# 19_USB_schdoc.net
KiCad netlist of a schematic drawn in Altium Designer
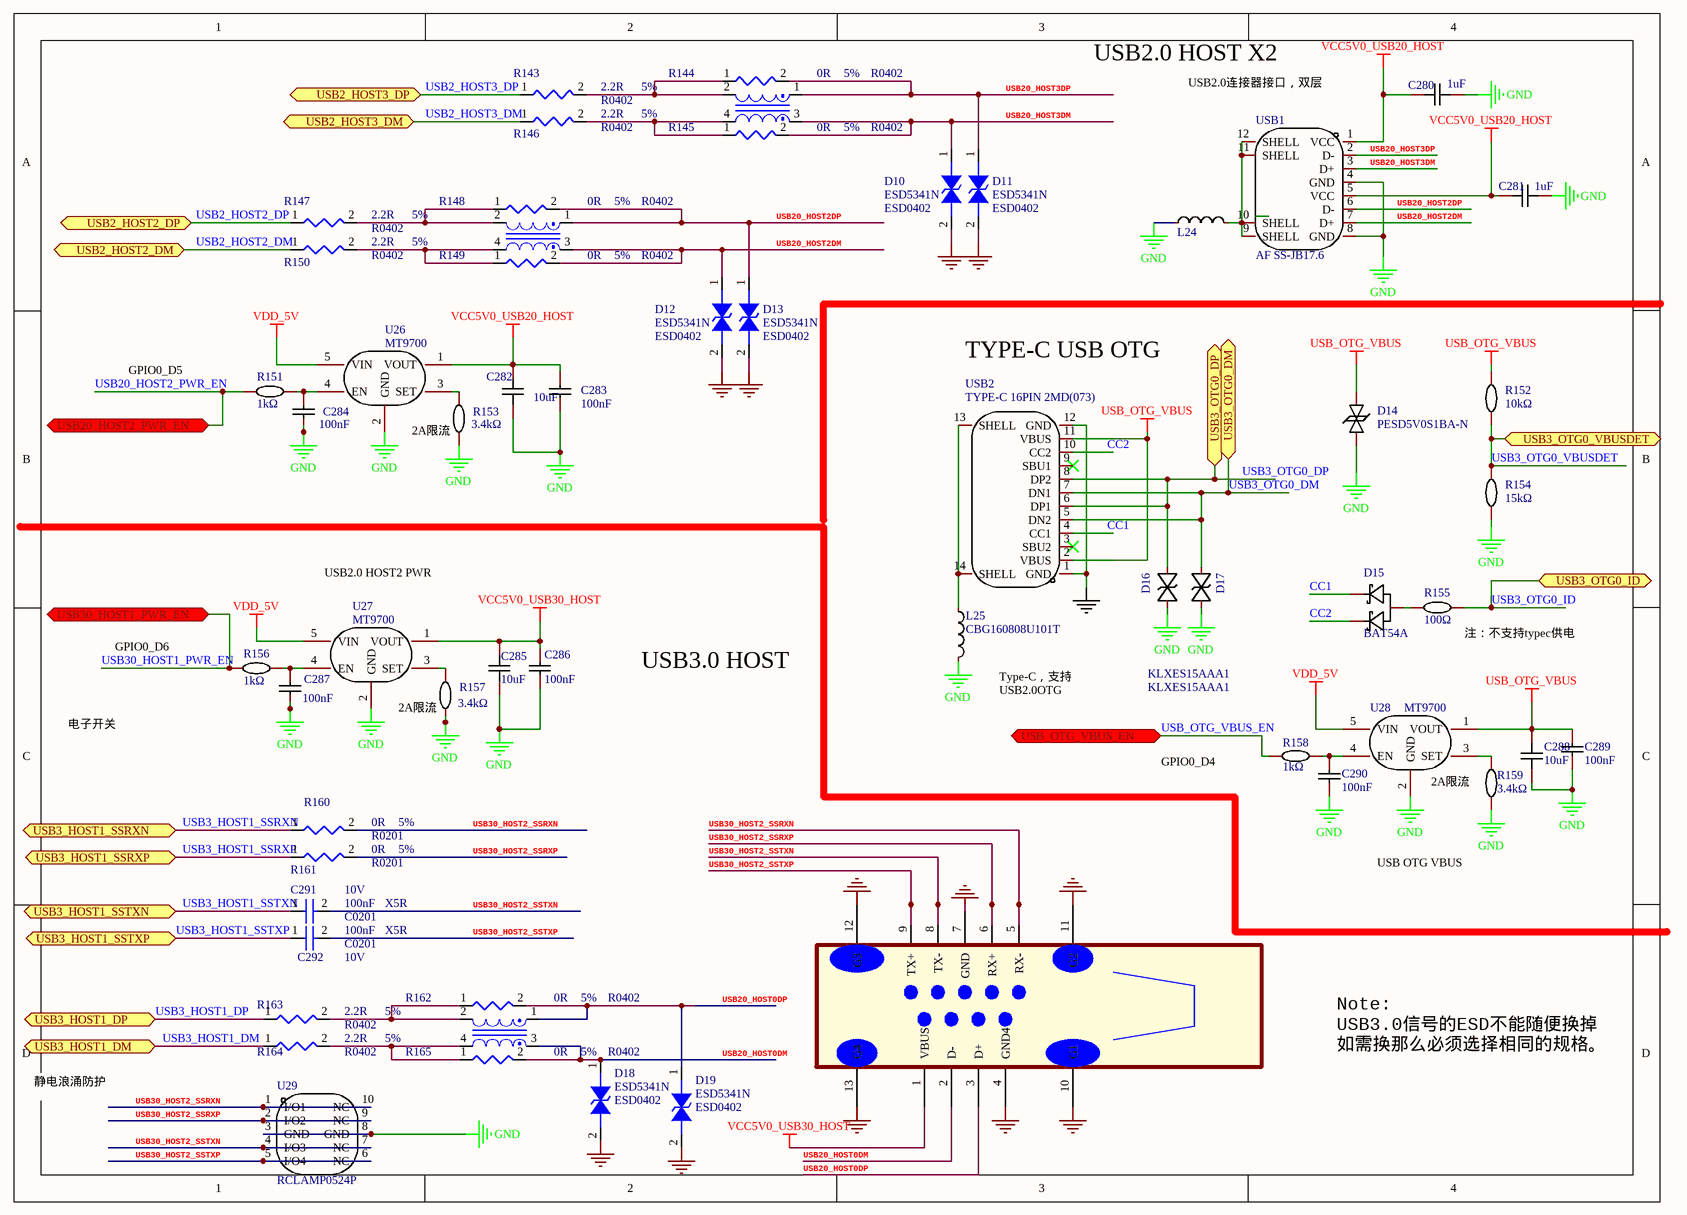
[diagram p0: 19_USB接口.schdoc.schdoc]

(export (version "E")
  (design (tool "Eeschema 10.0.6"))
  (components
    (comp (ref "C280")
      (value "1uF")
      (footprint "C0603")
      (fields
        (field (name "NAME") "1uF")
        (field (name "MANUFACTURER") "FH(风华)")
        (field (name "MANUFACTURER PART") "0603X105K100NT")
        (field (name "TOLERANCE") "±10%")
      )
      (libsource (lib "altium-import") (part "root_2_0603X105K100NT_"))
    )
    (comp (ref "C281")
      (value "1uF")
      (footprint "C0603")
      (fields
        (field (name "NAME") "1uF")
        (field (name "MANUFACTURER") "FH(风华)")
        (field (name "MANUFACTURER PART") "0603X105K100NT")
        (field (name "TOLERANCE") "±10%")
      )
      (libsource (lib "altium-import") (part "root_2_0603X105K100NT_"))
    )
    (comp (ref "C282")
      (value "10uF")
      (footprint "C0603")
      (fields
        (field (name "NAME") "10uF")
        (field (name "MANUFACTURER") "SAMSUNG(三星)")
        (field (name "MANUFACTURER PART") "CL10A106KP8NNNC")
        (field (name "TOLERANCE") "±10%")
      )
      (libsource (lib "altium-import") (part "root_3_CL10A106KP8NNNC_"))
    )
    (comp (ref "C283")
      (value "100nF")
      (footprint "C0603")
      (fields
        (field (name "NAME") "100nF")
        (field (name "MANUFACTURER") "FH(风华)")
        (field (name "MANUFACTURER PART") "0603B104K500NT")
        (field (name "TOLERANCE") "±10%")
      )
      (libsource (lib "altium-import") (part "root_3_0603B104K500NT_"))
    )
    (comp (ref "C284")
      (value "100nF")
      (footprint "C0603")
      (fields
        (field (name "NAME") "100nF")
        (field (name "MANUFACTURER") "FH(风华)")
        (field (name "MANUFACTURER PART") "0603B104K500NT")
        (field (name "TOLERANCE") "±10%")
      )
      (libsource (lib "altium-import") (part "root_1_0603B104K500NT_"))
    )
    (comp (ref "C285")
      (value "10uF")
      (footprint "C0603")
      (fields
        (field (name "NAME") "10uF")
        (field (name "MANUFACTURER") "SAMSUNG(三星)")
        (field (name "MANUFACTURER PART") "CL10A106KP8NNNC")
        (field (name "TOLERANCE") "±10%")
      )
      (libsource (lib "altium-import") (part "root_3_CL10A106KP8NNNC_"))
    )
    (comp (ref "C286")
      (value "100nF")
      (footprint "C0603")
      (fields
        (field (name "NAME") "100nF")
        (field (name "MANUFACTURER") "FH(风华)")
        (field (name "MANUFACTURER PART") "0603B104K500NT")
        (field (name "TOLERANCE") "±10%")
      )
      (libsource (lib "altium-import") (part "root_3_0603B104K500NT_"))
    )
    (comp (ref "C287")
      (value "100nF")
      (footprint "C0603")
      (fields
        (field (name "NAME") "100nF")
        (field (name "MANUFACTURER") "FH(风华)")
        (field (name "MANUFACTURER PART") "0603B104K500NT")
        (field (name "TOLERANCE") "±10%")
      )
      (libsource (lib "altium-import") (part "root_1_0603B104K500NT_"))
    )
    (comp (ref "C288")
      (value "10uF")
      (footprint "C0603")
      (fields
        (field (name "NAME") "10uF")
        (field (name "MANUFACTURER") "SAMSUNG(三星)")
        (field (name "MANUFACTURER PART") "CL10A106KP8NNNC")
        (field (name "TOLERANCE") "±10%")
      )
      (libsource (lib "altium-import") (part "root_3_CL10A106KP8NNNC_"))
    )
    (comp (ref "C289")
      (value "100nF")
      (footprint "C0603")
      (fields
        (field (name "NAME") "100nF")
        (field (name "MANUFACTURER") "FH(风华)")
        (field (name "MANUFACTURER PART") "0603B104K500NT")
        (field (name "TOLERANCE") "±10%")
      )
      (libsource (lib "altium-import") (part "root_3_0603B104K500NT_"))
    )
    (comp (ref "C290")
      (value "100nF")
      (footprint "C0603")
      (fields
        (field (name "NAME") "100nF")
        (field (name "MANUFACTURER") "FH(风华)")
        (field (name "MANUFACTURER PART") "0603B104K500NT")
        (field (name "TOLERANCE") "±10%")
      )
      (libsource (lib "altium-import") (part "root_1_0603B104K500NT_"))
    )
    (comp (ref "C291")
      (value "100nF")
      (footprint "C0201")
      (description "cap,100.00nF,+/-10%,10V,X5R,C0201")
      (fields
        (field (name "VOLTAGE") "10V")
        (field (name "PCB FOOTPRINT") "C0201")
        (field (name "DIELECTRIC") "X5R")
        (field (name "MANUFACTURER") "TDK")
        (field (name "TOLERANCE") "10%")
        (field (name "CREATED BY") "JJJ")
      )
      (libsource (lib "*") (part "CAP NP"))
    )
    (comp (ref "C292")
      (value "100nF")
      (footprint "C0201")
      (description "cap,100.00nF,+/-10%,10V,X5R,C0201")
      (fields
        (field (name "VOLTAGE") "10V")
        (field (name "PCB FOOTPRINT") "C0201")
        (field (name "DIELECTRIC") "X5R")
        (field (name "MANUFACTURER") "TDK")
        (field (name "TOLERANCE") "10%")
        (field (name "CREATED BY") "JJJ")
      )
      (libsource (lib "*") (part "CAP NP"))
    )
    (comp (ref "D10")
      (value "ESD5341N")
      (footprint "ESD0402")
      (description "1-Line, Bi-directional, Transient Voltage Suppressors.1pF.")
      (fields
        (field (name "PCB FOOTPRINT") "ESD0402")
        (field (name "MANUFACTURER") "WillSemi(韦尔半导体)")
        (field (name "CREATED BY") "JJJ")
      )
      (libsource (lib "*") (part "DIODE BI_DIR TRIG"))
    )
    (comp (ref "D11")
      (value "ESD5341N")
      (footprint "ESD0402")
      (description "1-Line, Bi-directional, Transient Voltage Suppressors.1pF.")
      (fields
        (field (name "PCB FOOTPRINT") "ESD0402")
        (field (name "MANUFACTURER") "WillSemi(韦尔半导体)")
        (field (name "CREATED BY") "JJJ")
      )
      (libsource (lib "*") (part "DIODE BI_DIR TRIG"))
    )
    (comp (ref "D12")
      (value "ESD5341N")
      (footprint "ESD0402")
      (description "1-Line, Bi-directional, Transient Voltage Suppressors.1pF.")
      (fields
        (field (name "PCB FOOTPRINT") "ESD0402")
        (field (name "MANUFACTURER") "WillSemi(韦尔半导体)")
        (field (name "CREATED BY") "JJJ")
      )
      (libsource (lib "*") (part "DIODE BI_DIR TRIG"))
    )
    (comp (ref "D13")
      (value "ESD5341N")
      (footprint "ESD0402")
      (description "1-Line, Bi-directional, Transient Voltage Suppressors.1pF.")
      (fields
        (field (name "PCB FOOTPRINT") "ESD0402")
        (field (name "MANUFACTURER") "WillSemi(韦尔半导体)")
        (field (name "CREATED BY") "JJJ")
      )
      (libsource (lib "*") (part "DIODE BI_DIR TRIG"))
    )
    (comp (ref "D14")
      (value "PESD5V0S1BA-N")
      (footprint "SOD-323_L1.8-W1.3-LS2.5-BI")
      (fields (field (name "NAME") "PESD5V0S1BA-N") (field (name "MANUFACTURER") "BORN(伯恩半导体)"))
      (libsource (lib "altium-import") (part "root_1_PESD5V0S1BA-N_"))
    )
    (comp (ref "D15")
      (value "BAT54A")
      (footprint "SOT-23-3_L2.9-W1.3-P1.90-LS2.4-BR")
      (fields (field (name "NAME") "BAT54A") (field (name "MANUFACTURER") "TWGMC(台湾迪嘉)"))
      (libsource (lib "altium-import") (part "root_3_BAT54A_C727124_"))
    )
    (comp (ref "D16")
      (value "KLXES15AAA1")
      (footprint "D0402-BI")
      (fields (field (name "NAME") "KLXES15AAA1") (field (name "MANUFACTURER") "KUU"))
      (libsource (lib "altium-import") (part "root_3_mirrored_KLXES15AAA1_"))
    )
    (comp (ref "D17")
      (value "KLXES15AAA1")
      (footprint "D0402-BI")
      (fields (field (name "NAME") "KLXES15AAA1") (field (name "MANUFACTURER") "KUU"))
      (libsource (lib "altium-import") (part "root_3_mirrored_KLXES15AAA1_"))
    )
    (comp (ref "D18")
      (value "ESD5341N")
      (footprint "ESD0402")
      (description "1-Line, Bi-directional, Transient Voltage Suppressors.1pF.")
      (fields
        (field (name "PCB FOOTPRINT") "ESD0402")
        (field (name "MANUFACTURER") "WillSemi(韦尔半导体)")
        (field (name "CREATED BY") "JJJ")
      )
      (libsource (lib "*") (part "DIODE BI_DIR TRIG"))
    )
    (comp (ref "D19")
      (value "ESD5341N")
      (footprint "ESD0402")
      (description "1-Line, Bi-directional, Transient Voltage Suppressors.1pF.")
      (fields
        (field (name "PCB FOOTPRINT") "ESD0402")
        (field (name "MANUFACTURER") "WillSemi(韦尔半导体)")
        (field (name "CREATED BY") "JJJ")
      )
      (libsource (lib "*") (part "DIODE BI_DIR TRIG"))
    )
    (comp (ref "J1")
      (value "USB30_TYPE_A_V_2")
      (footprint "USB30A9_25R70X7R32X13R85")
      (libsource (lib "RK3568核心板") (part "USB30_TYPE_A_V_2"))
    )
    (comp (ref "L22")
      (value "INDUCTOR COM")
      (footprint "RK3568核心板-13:RP2_0405")
      (libsource (lib "RK3568核心板") (part "INDUCTOR COM"))
    )
    (comp (ref "L23")
      (value "INDUCTOR COM")
      (footprint "RK3568核心板-13:RP2_0405")
      (libsource (lib "RK3568核心板") (part "INDUCTOR COM"))
    )
    (comp (ref "L24")
      (value "CBG160808U101T")
      (footprint "L0603")
      (fields (field (name "MANUFACTURER") "FH(风华)") (field (name "TOLERANCE") "±25%"))
      (libsource (lib "altium-import") (part "root_0_CBG160808U101T_"))
    )
    (comp (ref "L25")
      (value "CBG160808U101T")
      (footprint "L0603")
      (fields
        (field (name "NAME") "CBG160808U101T")
        (field (name "MANUFACTURER") "FH(风华)")
        (field (name "TOLERANCE") "±25%")
      )
      (libsource (lib "altium-import") (part "root_3_CBG160808U101T_"))
    )
    (comp (ref "L26")
      (value "INDUCTOR COM")
      (footprint "RK3568核心板-13:RP2_0405")
      (libsource (lib "RK3568核心板") (part "INDUCTOR COM"))
    )
    (comp (ref "R143")
      (value "2.2R")
      (footprint "R0402")
      (description "通用厚膜电阻,2R2,+/-5%,R0402,1/16W.")
      (fields
        (field (name "PCB FOOTPRINT") "R0402")
        (field (name "TOLERANCE") "5%")
        (field (name "MANUFACTURER") "YAGEO")
        (field (name "CREATED BY") "YTL")
      )
      (libsource (lib "*") (part "RESISTOR_Dup1"))
    )
    (comp (ref "R144")
      (value "0R")
      (footprint "R0402")
      (description "通用厚膜电阻,0R,+/-5%,R0402,1/16W.")
      (fields
        (field (name "PCB FOOTPRINT") "R0402")
        (field (name "TOLERANCE") "5%")
        (field (name "MANUFACTURER") "YAGEO")
        (field (name "CREATED BY") "YTL")
      )
      (libsource (lib "*") (part "RESISTOR_Dup1"))
    )
    (comp (ref "R145")
      (value "0R")
      (footprint "R0402")
      (description "通用厚膜电阻,0R,+/-5%,R0402,1/16W.")
      (fields
        (field (name "PCB FOOTPRINT") "R0402")
        (field (name "TOLERANCE") "5%")
        (field (name "MANUFACTURER") "YAGEO")
        (field (name "CREATED BY") "YTL")
      )
      (libsource (lib "*") (part "RESISTOR_Dup1"))
    )
    (comp (ref "R146")
      (value "2.2R")
      (footprint "R0402")
      (description "通用厚膜电阻,2R2,+/-5%,R0402,1/16W.")
      (fields
        (field (name "PCB FOOTPRINT") "R0402")
        (field (name "TOLERANCE") "5%")
        (field (name "MANUFACTURER") "YAGEO")
        (field (name "CREATED BY") "YTL")
      )
      (libsource (lib "*") (part "RESISTOR_Dup1"))
    )
    (comp (ref "R147")
      (value "2.2R")
      (footprint "R0402")
      (description "通用厚膜电阻,2R2,+/-5%,R0402,1/16W.")
      (fields
        (field (name "PCB FOOTPRINT") "R0402")
        (field (name "TOLERANCE") "5%")
        (field (name "MANUFACTURER") "YAGEO")
        (field (name "CREATED BY") "YTL")
      )
      (libsource (lib "*") (part "RESISTOR_Dup1"))
    )
    (comp (ref "R148")
      (value "0R")
      (footprint "R0402")
      (description "通用厚膜电阻,0R,+/-5%,R0402,1/16W.")
      (fields
        (field (name "PCB FOOTPRINT") "R0402")
        (field (name "TOLERANCE") "5%")
        (field (name "MANUFACTURER") "YAGEO")
        (field (name "CREATED BY") "YTL")
      )
      (libsource (lib "*") (part "RESISTOR_Dup1"))
    )
    (comp (ref "R149")
      (value "0R")
      (footprint "R0402")
      (description "通用厚膜电阻,0R,+/-5%,R0402,1/16W.")
      (fields
        (field (name "PCB FOOTPRINT") "R0402")
        (field (name "TOLERANCE") "5%")
        (field (name "MANUFACTURER") "YAGEO")
        (field (name "CREATED BY") "YTL")
      )
      (libsource (lib "*") (part "RESISTOR_Dup1"))
    )
    (comp (ref "R150")
      (value "2.2R")
      (footprint "R0402")
      (description "通用厚膜电阻,2R2,+/-5%,R0402,1/16W.")
      (fields
        (field (name "PCB FOOTPRINT") "R0402")
        (field (name "TOLERANCE") "5%")
        (field (name "MANUFACTURER") "YAGEO")
        (field (name "CREATED BY") "YTL")
      )
      (libsource (lib "*") (part "RESISTOR_Dup1"))
    )
    (comp (ref "R151")
      (value "1kΩ")
      (footprint "R0603")
      (fields
        (field (name "NAME") "1kΩ")
        (field (name "MANUFACTURER") "UNI-ROYAL(厚声)")
        (field (name "MANUFACTURER PART") "0603WAF1001T5E")
        (field (name "TOLERANCE") "±1%")
      )
      (libsource (lib "altium-import") (part "root_2_0603WAF1001T5E_"))
    )
    (comp (ref "R152")
      (value "10kΩ")
      (footprint "R0603")
      (fields
        (field (name "NAME") "10kΩ")
        (field (name "MANUFACTURER") "UNI-ROYAL(厚声)")
        (field (name "MANUFACTURER PART") "0603WAF1002T5E")
        (field (name "TOLERANCE") "±1%")
      )
      (libsource (lib "altium-import") (part "root_1_0603WAF1002T5E_"))
    )
    (comp (ref "R153")
      (value "3.4kΩ")
      (footprint "R0603")
      (fields
        (field (name "NAME") "3.4kΩ")
        (field (name "MANUFACTURER") "UNI-ROYAL(厚声)")
        (field (name "MANUFACTURER PART") "0603WAF3401T5E")
        (field (name "TOLERANCE") "±1%")
      )
      (libsource (lib "altium-import") (part "root_1_0603WAF3401T5E_"))
    )
    (comp (ref "R154")
      (value "15kΩ")
      (footprint "R0603")
      (fields
        (field (name "NAME") "15kΩ")
        (field (name "MANUFACTURER") "UNI-ROYAL(厚声)")
        (field (name "MANUFACTURER PART") "0603WAF1502T5E")
        (field (name "TOLERANCE") "±1%")
      )
      (libsource (lib "altium-import") (part "root_1_0603WAF1502T5E_"))
    )
    (comp (ref "R155")
      (value "100Ω")
      (footprint "R0603")
      (fields
        (field (name "NAME") "100Ω")
        (field (name "MANUFACTURER") "YAGEO(国巨)")
        (field (name "MANUFACTURER PART") "RC0603FR-07100RL")
        (field (name "TOLERANCE") "±1%")
      )
      (libsource (lib "altium-import") (part "root_0_RC0603FR-07100RL_"))
    )
    (comp (ref "R156")
      (value "1kΩ")
      (footprint "R0603")
      (fields
        (field (name "NAME") "1kΩ")
        (field (name "MANUFACTURER") "UNI-ROYAL(厚声)")
        (field (name "MANUFACTURER PART") "0603WAF1001T5E")
        (field (name "TOLERANCE") "±1%")
      )
      (libsource (lib "altium-import") (part "root_2_0603WAF1001T5E_"))
    )
    (comp (ref "R157")
      (value "3.4kΩ")
      (footprint "R0603")
      (fields
        (field (name "NAME") "3.4kΩ")
        (field (name "MANUFACTURER") "UNI-ROYAL(厚声)")
        (field (name "MANUFACTURER PART") "0603WAF3401T5E")
        (field (name "TOLERANCE") "±1%")
      )
      (libsource (lib "altium-import") (part "root_1_0603WAF3401T5E_"))
    )
    (comp (ref "R158")
      (value "1kΩ")
      (footprint "R0603")
      (fields
        (field (name "NAME") "1kΩ")
        (field (name "MANUFACTURER") "UNI-ROYAL(厚声)")
        (field (name "MANUFACTURER PART") "0603WAF1001T5E")
        (field (name "TOLERANCE") "±1%")
      )
      (libsource (lib "altium-import") (part "root_2_0603WAF1001T5E_"))
    )
    (comp (ref "R159")
      (value "3.4kΩ")
      (footprint "R0603")
      (fields
        (field (name "NAME") "3.4kΩ")
        (field (name "MANUFACTURER") "UNI-ROYAL(厚声)")
        (field (name "MANUFACTURER PART") "0603WAF3401T5E")
        (field (name "TOLERANCE") "±1%")
      )
      (libsource (lib "altium-import") (part "root_1_0603WAF3401T5E_"))
    )
    (comp (ref "R160")
      (value "0R")
      (footprint "R0402")
      (description "通用厚膜电阻,0R,+/-5%,R0201,1/20W.")
      (fields
        (field (name "PCB FOOTPRINT") "R0201")
        (field (name "TOLERANCE") "5%")
        (field (name "MANUFACTURER") "YAGEO")
        (field (name "CREATED BY") "YTL")
      )
      (libsource (lib "*") (part "RESISTOR_Dup1"))
    )
    (comp (ref "R161")
      (value "0R")
      (footprint "R0402")
      (description "通用厚膜电阻,0R,+/-5%,R0201,1/20W.")
      (fields
        (field (name "PCB FOOTPRINT") "R0201")
        (field (name "TOLERANCE") "5%")
        (field (name "MANUFACTURER") "YAGEO")
        (field (name "CREATED BY") "YTL")
      )
      (libsource (lib "*") (part "RESISTOR_Dup1"))
    )
    (comp (ref "R162")
      (value "0R")
      (footprint "R0402")
      (description "通用厚膜电阻,0R,+/-5%,R0402,1/16W.")
      (fields
        (field (name "PCB FOOTPRINT") "R0402")
        (field (name "TOLERANCE") "5%")
        (field (name "MANUFACTURER") "YAGEO")
        (field (name "CREATED BY") "YTL")
      )
      (libsource (lib "*") (part "RESISTOR_Dup1"))
    )
    (comp (ref "R163")
      (value "2.2R")
      (footprint "R0402")
      (description "通用厚膜电阻,2R2,+/-5%,R0402,1/16W.")
      (fields
        (field (name "PCB FOOTPRINT") "R0402")
        (field (name "TOLERANCE") "5%")
        (field (name "MANUFACTURER") "YAGEO")
        (field (name "CREATED BY") "YTL")
      )
      (libsource (lib "*") (part "RESISTOR_Dup1"))
    )
    (comp (ref "R164")
      (value "2.2R")
      (footprint "R0402")
      (description "通用厚膜电阻,2R2,+/-5%,R0402,1/16W.")
      (fields
        (field (name "PCB FOOTPRINT") "R0402")
        (field (name "TOLERANCE") "5%")
        (field (name "MANUFACTURER") "YAGEO")
        (field (name "CREATED BY") "YTL")
      )
      (libsource (lib "*") (part "RESISTOR_Dup1"))
    )
    (comp (ref "R165")
      (value "0R")
      (footprint "R0402")
      (description "通用厚膜电阻,0R,+/-5%,R0402,1/16W.")
      (fields
        (field (name "PCB FOOTPRINT") "R0402")
        (field (name "TOLERANCE") "5%")
        (field (name "MANUFACTURER") "YAGEO")
        (field (name "CREATED BY") "YTL")
      )
      (libsource (lib "*") (part "RESISTOR_Dup1"))
    )
    (comp (ref "U26")
      (value "MT9700")
      (footprint "SOT-23-5_L3.0-W1.7-P0.95-LS2.8-BR")
      (fields (field (name "NAME") "MT9700") (field (name "MANUFACTURER") "西安航天民芯"))
      (libsource (lib "altium-import") (part "root_0_mirrored_MT9700_"))
    )
    (comp (ref "U27")
      (value "MT9700")
      (footprint "SOT-23-5_L3.0-W1.7-P0.95-LS2.8-BR")
      (fields (field (name "NAME") "MT9700") (field (name "MANUFACTURER") "西安航天民芯"))
      (libsource (lib "altium-import") (part "root_0_mirrored_MT9700_"))
    )
    (comp (ref "U28")
      (value "MT9700")
      (footprint "SOT-23-5_L3.0-W1.7-P0.95-LS2.8-BR")
      (fields (field (name "NAME") "MT9700") (field (name "MANUFACTURER") "西安航天民芯"))
      (libsource (lib "altium-import") (part "root_0_mirrored_MT9700_"))
    )
    (comp (ref "U29")
      (value "RCLAMP0524P")
      (footprint "DFN2510-10_L2.5-W1.0-P0.50-BL")
      (fields (field (name "NAME") "RCLAMP0524P") (field (name "MANUFACTURER") "TECH PUBLIC(台舟)"))
      (libsource (lib "altium-import") (part "root_0_RCLAMP0524P_C907837_"))
    )
    (comp (ref "USB1")
      (value "AF SS-JB17.6")
      (footprint "USB-A-TH_AF-SS-JB17.6")
      (fields (field (name "NAME") "AF SS-JB17.6") (field (name "MANUFACTURER") "SHOU HAN(首韩)"))
      (libsource (lib "altium-import") (part "root_0_mirrored_AF SS-JB17.6_"))
    )
    (comp (ref "USB2")
      (value "TYPE-C 16PIN 2MD(073)")
      (footprint "USB-C-SMD_TYPE-C-6PIN-2MD-073")
      (fields (field (name "NAME") "TYPE-C 16PIN 2MD(073)") (field (name "MANUFACTURER") "SHOU HAN(首韩)"))
      (libsource (lib "altium-import") (part "root_2_TYPE-C 16PIN 2MD(073)_"))
    )
  )
  (nets
    (net (code "1") (name "/CC1") (class "Default")
      (node (ref "D15") (pin "1") (pinfunction "A_1") (pintype "passive"))
      (node (ref "USB2") (pin "4") (pinfunction "CC1_4") (pintype "passive"))
    )
    (net (code "2") (name "/CC2") (class "Default")
      (node (ref "D15") (pin "2") (pinfunction "A_2") (pintype "passive"))
      (node (ref "USB2") (pin "10") (pinfunction "CC2_10") (pintype "passive"))
    )
    (net (code "3") (name "/USB2_HOST2_DM") (class "Default")
      (node (ref "R150") (pin "1") (pinfunction "1_1") (pintype "passive"))
    )
    (net (code "4") (name "/USB2_HOST2_DP") (class "Default")
      (node (ref "R147") (pin "1") (pinfunction "1_1") (pintype "passive"))
    )
    (net (code "5") (name "/USB2_HOST3_DM") (class "Default")
      (node (ref "R146") (pin "1") (pinfunction "1_1") (pintype "passive"))
    )
    (net (code "6") (name "/USB2_HOST3_DP") (class "Default")
      (node (ref "R143") (pin "1") (pinfunction "1_1") (pintype "passive"))
    )
    (net (code "7") (name "/USB3_HOST1_DM") (class "Default")
      (node (ref "R164") (pin "1") (pinfunction "1_1") (pintype "passive"))
    )
    (net (code "8") (name "/USB3_HOST1_DP") (class "Default")
      (node (ref "R163") (pin "1") (pinfunction "1_1") (pintype "passive"))
    )
    (net (code "9") (name "/USB3_HOST1_SSRXN") (class "Default")
      (node (ref "R160") (pin "1") (pinfunction "1_1") (pintype "passive"))
    )
    (net (code "10") (name "/USB3_HOST1_SSRXP") (class "Default")
      (node (ref "R161") (pin "1") (pinfunction "1_1") (pintype "passive"))
    )
    (net (code "11") (name "/USB3_HOST1_SSTXN") (class "Default")
      (node (ref "C291") (pin "1") (pinfunction "1_1") (pintype "passive"))
    )
    (net (code "12") (name "/USB3_HOST1_SSTXP") (class "Default")
      (node (ref "C292") (pin "1") (pinfunction "1_1") (pintype "passive"))
    )
    (net (code "13") (name "/USB3_OTG0_DM") (class "Default")
      (node (ref "D17") (pin "1") (pinfunction "K_1") (pintype "passive"))
      (node (ref "USB2") (pin "5") (pinfunction "DN2_5") (pintype "passive"))
      (node (ref "USB2") (pin "7") (pinfunction "DN1_7") (pintype "passive"))
    )
    (net (code "14") (name "/USB3_OTG0_DP") (class "Default")
      (node (ref "D16") (pin "1") (pinfunction "K_1") (pintype "passive"))
      (node (ref "USB2") (pin "6") (pinfunction "DP1_6") (pintype "passive"))
      (node (ref "USB2") (pin "8") (pinfunction "DP2_8") (pintype "passive"))
    )
    (net (code "15") (name "/USB3_OTG0_ID") (class "Default")
      (node (ref "R155") (pin "2") (pinfunction "2_2") (pintype "passive"))
    )
    (net (code "16") (name "/USB3_OTG0_VBUSDET") (class "Default")
      (node (ref "R152") (pin "1") (pinfunction "1_1") (pintype "passive"))
      (node (ref "R154") (pin "2") (pinfunction "2_2") (pintype "passive"))
    )
    (net (code "17") (name "/USB20_HOST0DM") (class "Default")
      (node (ref "D18") (pin "1") (pinfunction "1_1") (pintype "passive"))
      (node (ref "J1") (pin "2") (pinfunction "D-_2") (pintype "passive"))
      (node (ref "L26") (pin "3") (pinfunction "3_3") (pintype "passive"))
      (node (ref "R165") (pin "2") (pinfunction "2_2") (pintype "passive"))
    )
    (net (code "18") (name "/USB20_HOST0DP") (class "Default")
      (node (ref "D19") (pin "1") (pinfunction "1_1") (pintype "passive"))
      (node (ref "J1") (pin "3") (pinfunction "D+_3") (pintype "passive"))
      (node (ref "L26") (pin "1") (pinfunction "1_1") (pintype "passive"))
      (node (ref "R162") (pin "2") (pinfunction "2_2") (pintype "passive"))
    )
    (net (code "19") (name "/USB20_HOST2DM") (class "Default")
      (node (ref "D12") (pin "1") (pinfunction "1_1") (pintype "passive"))
      (node (ref "L23") (pin "3") (pinfunction "3_3") (pintype "passive"))
      (node (ref "R149") (pin "2") (pinfunction "2_2") (pintype "passive"))
      (node (ref "USB1") (pin "7") (pinfunction "D+_7") (pintype "passive"))
    )
    (net (code "20") (name "/USB20_HOST2DP") (class "Default")
      (node (ref "D13") (pin "1") (pinfunction "1_1") (pintype "passive"))
      (node (ref "L23") (pin "1") (pinfunction "1_1") (pintype "passive"))
      (node (ref "R148") (pin "2") (pinfunction "2_2") (pintype "passive"))
      (node (ref "USB1") (pin "6") (pinfunction "D-_6") (pintype "passive"))
    )
    (net (code "21") (name "/USB20_HOST2_PWR_EN") (class "Default")
      (node (ref "R151") (pin "2") (pinfunction "2_2") (pintype "passive"))
    )
    (net (code "22") (name "/USB20_HOST3DM") (class "Default")
      (node (ref "D10") (pin "1") (pinfunction "1_1") (pintype "passive"))
      (node (ref "L22") (pin "3") (pinfunction "3_3") (pintype "passive"))
      (node (ref "R145") (pin "2") (pinfunction "2_2") (pintype "passive"))
      (node (ref "USB1") (pin "3") (pinfunction "D+_3") (pintype "passive"))
    )
    (net (code "23") (name "/USB20_HOST3DP") (class "Default")
      (node (ref "D11") (pin "1") (pinfunction "1_1") (pintype "passive"))
      (node (ref "L22") (pin "1") (pinfunction "1_1") (pintype "passive"))
      (node (ref "R144") (pin "2") (pinfunction "2_2") (pintype "passive"))
      (node (ref "USB1") (pin "2") (pinfunction "D-_2") (pintype "passive"))
    )
    (net (code "24") (name "/USB30_HOST1_PWR_EN") (class "Default")
      (node (ref "R156") (pin "2") (pinfunction "2_2") (pintype "passive"))
    )
    (net (code "25") (name "/USB30_HOST2_SSRXN") (class "Default")
      (node (ref "J1") (pin "5") (pinfunction "RX-_5") (pintype "passive"))
      (node (ref "R160") (pin "2") (pinfunction "2_2") (pintype "passive"))
      (node (ref "U29") (pin "1") (pinfunction "I/O1_1") (pintype "passive"))
      (node (ref "U29") (pin "10") (pinfunction "NC_10") (pintype "passive"))
    )
    (net (code "26") (name "/USB30_HOST2_SSRXP") (class "Default")
      (node (ref "J1") (pin "6") (pinfunction "RX+_6") (pintype "passive"))
      (node (ref "R161") (pin "2") (pinfunction "2_2") (pintype "passive"))
      (node (ref "U29") (pin "2") (pinfunction "I/O2_2") (pintype "passive"))
      (node (ref "U29") (pin "9") (pinfunction "NC_9") (pintype "passive"))
    )
    (net (code "27") (name "/USB30_HOST2_SSTXN") (class "Default")
      (node (ref "C291") (pin "2") (pinfunction "2_2") (pintype "passive"))
      (node (ref "J1") (pin "8") (pinfunction "TX-_8") (pintype "passive"))
      (node (ref "U29") (pin "4") (pinfunction "I/O3_4") (pintype "passive"))
      (node (ref "U29") (pin "7") (pinfunction "NC_7") (pintype "passive"))
    )
    (net (code "28") (name "/USB30_HOST2_SSTXP") (class "Default")
      (node (ref "C292") (pin "2") (pinfunction "2_2") (pintype "passive"))
      (node (ref "J1") (pin "9") (pinfunction "TX+_9") (pintype "passive"))
      (node (ref "U29") (pin "5") (pinfunction "I/O4_5") (pintype "passive"))
      (node (ref "U29") (pin "6") (pinfunction "NC_6") (pintype "passive"))
    )
    (net (code "29") (name "/USB_OTG_VBUS_EN") (class "Default")
      (node (ref "R158") (pin "2") (pinfunction "2_2") (pintype "passive"))
    )
    (net (code "30") (name "GND") (class "Default")
      (node (ref "C280") (pin "1") (pinfunction "1_1") (pintype "passive"))
      (node (ref "C281") (pin "1") (pinfunction "1_1") (pintype "passive"))
      (node (ref "C282") (pin "2") (pinfunction "2_2") (pintype "passive"))
      (node (ref "C283") (pin "2") (pinfunction "2_2") (pintype "passive"))
      (node (ref "C284") (pin "1") (pinfunction "1_1") (pintype "passive"))
      (node (ref "C285") (pin "2") (pinfunction "2_2") (pintype "passive"))
      (node (ref "C286") (pin "2") (pinfunction "2_2") (pintype "passive"))
      (node (ref "C287") (pin "1") (pinfunction "1_1") (pintype "passive"))
      (node (ref "C288") (pin "2") (pinfunction "2_2") (pintype "passive"))
      (node (ref "C289") (pin "2") (pinfunction "2_2") (pintype "passive"))
      (node (ref "C290") (pin "1") (pinfunction "1_1") (pintype "passive"))
      (node (ref "D10") (pin "2") (pinfunction "2_2") (pintype "passive"))
      (node (ref "D11") (pin "2") (pinfunction "2_2") (pintype "passive"))
      (node (ref "D12") (pin "2") (pinfunction "2_2") (pintype "passive"))
      (node (ref "D13") (pin "2") (pinfunction "2_2") (pintype "passive"))
      (node (ref "D14") (pin "1") (pinfunction "1_1") (pintype "passive"))
      (node (ref "D16") (pin "2") (pinfunction "A_2") (pintype "passive"))
      (node (ref "D17") (pin "2") (pinfunction "A_2") (pintype "passive"))
      (node (ref "D18") (pin "2") (pinfunction "2_2") (pintype "passive"))
      (node (ref "D19") (pin "2") (pinfunction "2_2") (pintype "passive"))
      (node (ref "J1") (pin "10") (pinfunction "G1_10") (pintype "passive"))
      (node (ref "J1") (pin "11") (pinfunction "G2_11") (pintype "passive"))
      (node (ref "J1") (pin "12") (pinfunction "G3_12") (pintype "passive"))
      (node (ref "J1") (pin "13") (pinfunction "G4_13") (pintype "passive"))
      (node (ref "J1") (pin "4") (pinfunction "GND4_4") (pintype "power_in"))
      (node (ref "J1") (pin "7") (pinfunction "GND_7") (pintype "power_in"))
      (node (ref "L24") (pin "1") (pinfunction "1_1") (pintype "passive"))
      (node (ref "L25") (pin "2") (pinfunction "2_2") (pintype "passive"))
      (node (ref "R153") (pin "1") (pinfunction "1_1") (pintype "passive"))
      (node (ref "R154") (pin "1") (pinfunction "1_1") (pintype "passive"))
      (node (ref "R157") (pin "1") (pinfunction "1_1") (pintype "passive"))
      (node (ref "R159") (pin "1") (pinfunction "1_1") (pintype "passive"))
      (node (ref "U26") (pin "2") (pinfunction "GND_2") (pintype "passive"))
      (node (ref "U27") (pin "2") (pinfunction "GND_2") (pintype "passive"))
      (node (ref "U28") (pin "2") (pinfunction "GND_2") (pintype "passive"))
      (node (ref "U29") (pin "3") (pinfunction "GND_3") (pintype "passive"))
      (node (ref "U29") (pin "8") (pinfunction "GND_8") (pintype "passive"))
      (node (ref "USB1") (pin "4") (pinfunction "GND_4") (pintype "passive"))
      (node (ref "USB1") (pin "8") (pinfunction "GND_8") (pintype "passive"))
      (node (ref "USB2") (pin "1") (pinfunction "GND_1") (pintype "passive"))
      (node (ref "USB2") (pin "12") (pinfunction "GND_12") (pintype "passive"))
    )
    (net (code "31") (name "Net-(D15-K)") (class "Default")
      (node (ref "D15") (pin "3") (pinfunction "K_3") (pintype "passive"))
      (node (ref "R155") (pin "1") (pinfunction "1_1") (pintype "passive"))
    )
    (net (code "32") (name "Net-(L22-Pad2)") (class "Default")
      (node (ref "L22") (pin "2") (pinfunction "2_2") (pintype "passive"))
      (node (ref "R143") (pin "2") (pinfunction "2_2") (pintype "passive"))
      (node (ref "R144") (pin "1") (pinfunction "1_1") (pintype "passive"))
    )
    (net (code "33") (name "Net-(L22-Pad4)") (class "Default")
      (node (ref "L22") (pin "4") (pinfunction "4_4") (pintype "passive"))
      (node (ref "R145") (pin "1") (pinfunction "1_1") (pintype "passive"))
      (node (ref "R146") (pin "2") (pinfunction "2_2") (pintype "passive"))
    )
    (net (code "34") (name "Net-(L23-Pad2)") (class "Default")
      (node (ref "L23") (pin "2") (pinfunction "2_2") (pintype "passive"))
      (node (ref "R147") (pin "2") (pinfunction "2_2") (pintype "passive"))
      (node (ref "R148") (pin "1") (pinfunction "1_1") (pintype "passive"))
    )
    (net (code "35") (name "Net-(L23-Pad4)") (class "Default")
      (node (ref "L23") (pin "4") (pinfunction "4_4") (pintype "passive"))
      (node (ref "R149") (pin "1") (pinfunction "1_1") (pintype "passive"))
      (node (ref "R150") (pin "2") (pinfunction "2_2") (pintype "passive"))
    )
    (net (code "36") (name "Net-(L24-Pad2)") (class "Default")
      (node (ref "L24") (pin "2") (pinfunction "2_2") (pintype "passive"))
      (node (ref "USB1") (pin "10") (pinfunction "SHELL_10") (pintype "passive"))
      (node (ref "USB1") (pin "11") (pinfunction "SHELL_11") (pintype "passive"))
      (node (ref "USB1") (pin "12") (pinfunction "SHELL_12") (pintype "passive"))
      (node (ref "USB1") (pin "9") (pinfunction "SHELL_9") (pintype "passive"))
    )
    (net (code "37") (name "Net-(L25-Pad1)") (class "Default")
      (node (ref "L25") (pin "1") (pinfunction "1_1") (pintype "passive"))
      (node (ref "USB2") (pin "13") (pinfunction "SHELL_13") (pintype "passive"))
      (node (ref "USB2") (pin "14") (pinfunction "SHELL_14") (pintype "passive"))
    )
    (net (code "38") (name "Net-(L26-Pad2)") (class "Default")
      (node (ref "L26") (pin "2") (pinfunction "2_2") (pintype "passive"))
      (node (ref "R162") (pin "1") (pinfunction "1_1") (pintype "passive"))
      (node (ref "R163") (pin "2") (pinfunction "2_2") (pintype "passive"))
    )
    (net (code "39") (name "Net-(L26-Pad4)") (class "Default")
      (node (ref "L26") (pin "4") (pinfunction "4_4") (pintype "passive"))
      (node (ref "R164") (pin "2") (pinfunction "2_2") (pintype "passive"))
      (node (ref "R165") (pin "1") (pinfunction "1_1") (pintype "passive"))
    )
    (net (code "40") (name "Net-(U26-EN)") (class "Default")
      (node (ref "C284") (pin "2") (pinfunction "2_2") (pintype "passive"))
      (node (ref "R151") (pin "1") (pinfunction "1_1") (pintype "passive"))
      (node (ref "U26") (pin "4") (pinfunction "EN_4") (pintype "passive"))
    )
    (net (code "41") (name "Net-(U26-SET)") (class "Default")
      (node (ref "R153") (pin "2") (pinfunction "2_2") (pintype "passive"))
      (node (ref "U26") (pin "3") (pinfunction "SET_3") (pintype "passive"))
    )
    (net (code "42") (name "Net-(U27-EN)") (class "Default")
      (node (ref "C287") (pin "2") (pinfunction "2_2") (pintype "passive"))
      (node (ref "R156") (pin "1") (pinfunction "1_1") (pintype "passive"))
      (node (ref "U27") (pin "4") (pinfunction "EN_4") (pintype "passive"))
    )
    (net (code "43") (name "Net-(U27-SET)") (class "Default")
      (node (ref "R157") (pin "2") (pinfunction "2_2") (pintype "passive"))
      (node (ref "U27") (pin "3") (pinfunction "SET_3") (pintype "passive"))
    )
    (net (code "44") (name "Net-(U28-EN)") (class "Default")
      (node (ref "C290") (pin "2") (pinfunction "2_2") (pintype "passive"))
      (node (ref "R158") (pin "1") (pinfunction "1_1") (pintype "passive"))
      (node (ref "U28") (pin "4") (pinfunction "EN_4") (pintype "passive"))
    )
    (net (code "45") (name "Net-(U28-SET)") (class "Default")
      (node (ref "R159") (pin "2") (pinfunction "2_2") (pintype "passive"))
      (node (ref "U28") (pin "3") (pinfunction "SET_3") (pintype "passive"))
    )
    (net (code "46") (name "USB_OTG_VBUS") (class "Default")
      (node (ref "C288") (pin "1") (pinfunction "1_1") (pintype "passive"))
      (node (ref "C289") (pin "1") (pinfunction "1_1") (pintype "passive"))
      (node (ref "D14") (pin "2") (pinfunction "2_2") (pintype "passive"))
      (node (ref "R152") (pin "2") (pinfunction "2_2") (pintype "passive"))
      (node (ref "U28") (pin "1") (pinfunction "VOUT_1") (pintype "passive"))
      (node (ref "USB2") (pin "11") (pinfunction "VBUS_11") (pintype "passive"))
      (node (ref "USB2") (pin "2") (pinfunction "VBUS_2") (pintype "passive"))
    )
    (net (code "47") (name "VCC5V0_USB20_HOST") (class "Default")
      (node (ref "C280") (pin "2") (pinfunction "2_2") (pintype "passive"))
      (node (ref "C281") (pin "2") (pinfunction "2_2") (pintype "passive"))
      (node (ref "C282") (pin "1") (pinfunction "1_1") (pintype "passive"))
      (node (ref "C283") (pin "1") (pinfunction "1_1") (pintype "passive"))
      (node (ref "U26") (pin "1") (pinfunction "VOUT_1") (pintype "passive"))
      (node (ref "USB1") (pin "1") (pinfunction "VCC_1") (pintype "passive"))
      (node (ref "USB1") (pin "5") (pinfunction "VCC_5") (pintype "passive"))
    )
    (net (code "48") (name "VCC5V0_USB30_HOST") (class "Default")
      (node (ref "C285") (pin "1") (pinfunction "1_1") (pintype "passive"))
      (node (ref "C286") (pin "1") (pinfunction "1_1") (pintype "passive"))
      (node (ref "J1") (pin "1") (pinfunction "VBUS_1") (pintype "power_in"))
      (node (ref "U27") (pin "1") (pinfunction "VOUT_1") (pintype "passive"))
    )
    (net (code "49") (name "VDD_5V") (class "Default")
      (node (ref "U26") (pin "5") (pinfunction "VIN_5") (pintype "passive"))
      (node (ref "U27") (pin "5") (pinfunction "VIN_5") (pintype "passive"))
      (node (ref "U28") (pin "5") (pinfunction "VIN_5") (pintype "passive"))
    )
    (net (code "50") (name "unconnected-(USB2-SBU1-Pad9)") (class "Default")
      (node (ref "USB2") (pin "9") (pinfunction "SBU1_9") (pintype "passive+no_connect"))
    )
    (net (code "51") (name "unconnected-(USB2-SBU2-Pad3)") (class "Default")
      (node (ref "USB2") (pin "3") (pinfunction "SBU2_3") (pintype "passive+no_connect"))
    )
  )
)
